# E17-04-ISO_SPI.net
KiCad netlist of a schematic drawn in Altium Designer
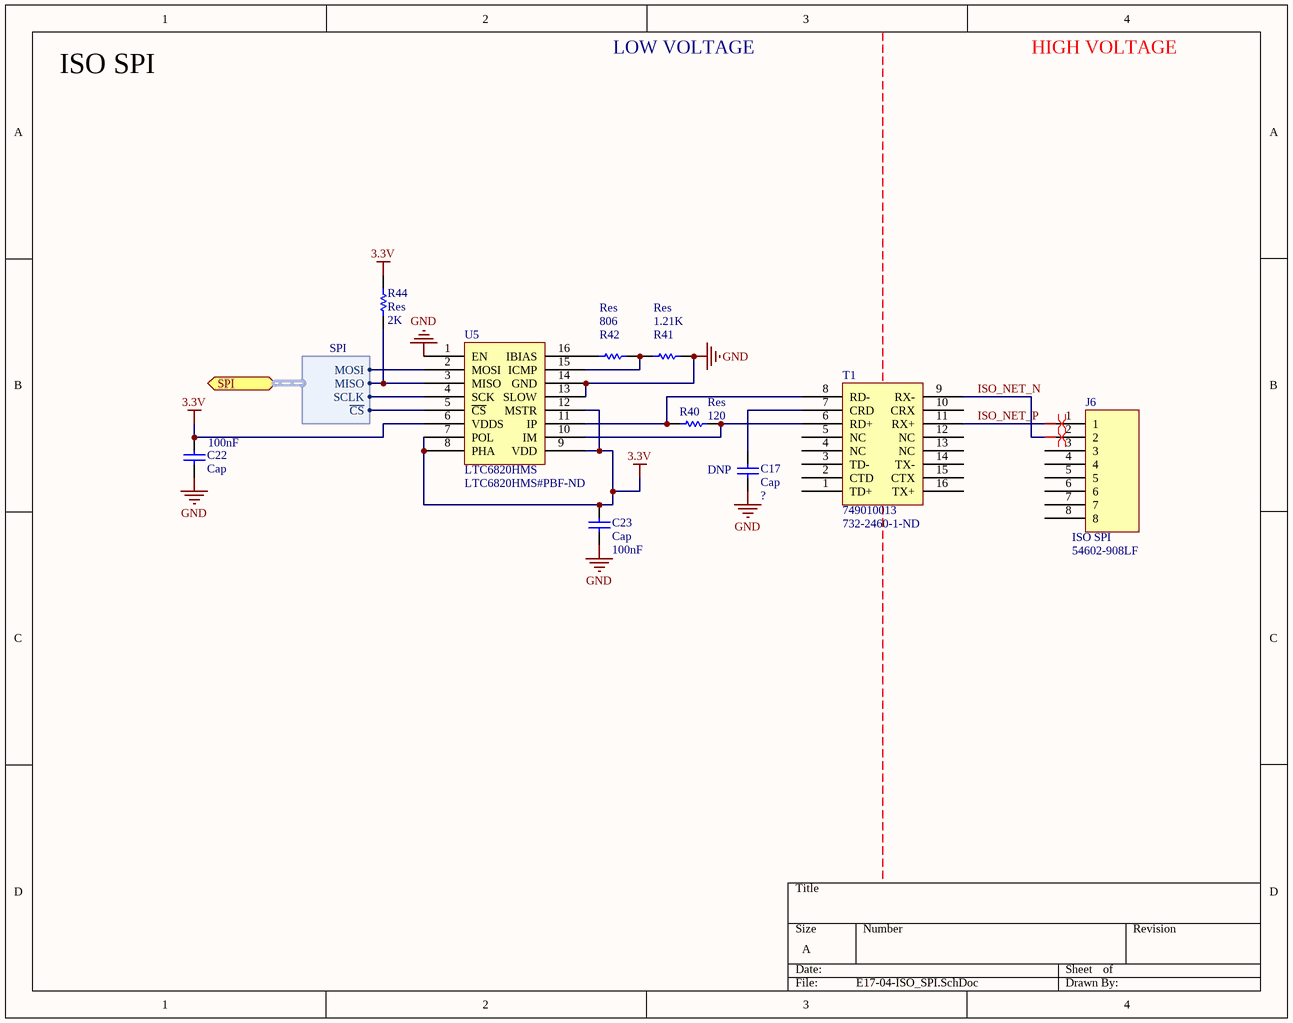
[diagram p0: E17-04-ISO_SPI.SchDoc]

(export (version "E")
  (design (tool "Eeschema 10.0.6"))
  (components
    (comp (ref "C17")
      (value "Cap")
      (footprint "C0805")
      (description "Capacitor")
      (fields
        (field (name "ALTIUM_VALUE") "?")
        (field (name "STUFF") "DNP")
        (field (name "PUBLISHER") "Altium Limited")
      )
      (libsource (lib "Capacitors") (part "Cap"))
    )
    (comp (ref "C22")
      (value "Cap")
      (footprint "C0805")
      (description "Capacitor")
      (fields (field (name "ALTIUM_VALUE") "100nF") (field (name "PUBLISHER") "Altium Limited"))
      (libsource (lib "Capacitors") (part "Cap"))
    )
    (comp (ref "C23")
      (value "Cap")
      (footprint "C0805")
      (description "Capacitor")
      (fields (field (name "ALTIUM_VALUE") "100nF") (field (name "PUBLISHER") "Altium Limited"))
      (libsource (lib "Capacitors") (part "Cap"))
    )
    (comp (ref "J6")
      (value "ISO SPI")
      (footprint "54602-908LF")
      (description "CONN MOD JACK R/A 8P8C")
      (fields (field (name "MPN") "54602-908LF"))
      (libsource (lib "Connectors and Headers") (part "54602-908LF"))
    )
    (comp (ref "R40")
      (value "Res")
      (footprint "2012[0805]")
      (description "Surface Mount Resistor")
      (fields (field (name "ALTIUM_VALUE") "120") (field (name "PUBLISHER") "Altium Limited"))
      (libsource (lib "Resistors") (part "Res"))
    )
    (comp (ref "R41")
      (value "Res")
      (footprint "2012[0805]")
      (description "Surface Mount Resistor")
      (fields (field (name "ALTIUM_VALUE") "1.21K") (field (name "PUBLISHER") "Altium Limited"))
      (libsource (lib "Resistors") (part "Res"))
    )
    (comp (ref "R42")
      (value "Res")
      (footprint "2012[0805]")
      (description "Surface Mount Resistor")
      (fields (field (name "ALTIUM_VALUE") "806") (field (name "PUBLISHER") "Altium Limited"))
      (libsource (lib "Resistors") (part "Res"))
    )
    (comp (ref "R44")
      (value "Res")
      (footprint "2012[0805]")
      (description "Surface Mount Resistor")
      (fields (field (name "ALTIUM_VALUE") "2K") (field (name "PUBLISHER") "Altium Limited"))
      (libsource (lib "Resistors") (part "Res"))
    )
    (comp (ref "T1")
      (value "749010013")
      (footprint "749010013")
      (description "TRANSFORMER LAN 10/100 SMD")
      (fields (field (name "SUPPLIER PART NUMBER 1") "732-2460-1-ND"))
      (libsource (lib "Isolation Circuits") (part "749010013"))
    )
    (comp (ref "U5")
      (value "LTC6820HMS")
      (footprint "LTC6820HMS")
      (description "IC COMM INTERFACE ISOSPI")
      (fields (field (name "SUPPLIER PART NUMBER 1") "LTC6820HMS#PBF-ND"))
      (libsource (lib "Isolation Circuits") (part "LTC6820HMS"))
    )
  )
  (nets
    (net (code "2") (name "/ISO_NET_N") (class "Default")
      (node (ref "J6") (pin "2") (pinfunction "2_2") (pintype "passive"))
      (node (ref "T1") (pin "9") (pinfunction "RX-_9") (pintype "passive"))
    )
    (net (code "3") (name "/ISO_NET_P") (class "Default")
      (node (ref "J6") (pin "1") (pinfunction "1_1") (pintype "passive"))
      (node (ref "T1") (pin "11") (pinfunction "RX+_11") (pintype "passive"))
    )
    (net (code "4") (name "/MISO") (class "Default")
      (node (ref "R44") (pin "2") (pinfunction "2_2") (pintype "passive"))
      (node (ref "U5") (pin "3") (pinfunction "MISO_3") (pintype "passive"))
    )
    (net (code "5") (name "/MOSI") (class "Default")
      (node (ref "U5") (pin "2") (pinfunction "MOSI_2") (pintype "passive"))
    )
    (net (code "6") (name "/SCLK") (class "Default")
      (node (ref "U5") (pin "4") (pinfunction "SCK_4") (pintype "passive"))
    )
    (net (code "8") (name "/~{CS}") (class "Default")
      (node (ref "U5") (pin "5") (pinfunction "~{CS}_5") (pintype "passive"))
    )
    (net (code "9") (name "3.3V") (class "Default")
      (node (ref "C22") (pin "2") (pinfunction "2_2") (pintype "passive"))
      (node (ref "C23") (pin "2") (pinfunction "2_2") (pintype "passive"))
      (node (ref "R44") (pin "1") (pinfunction "1_1") (pintype "passive"))
      (node (ref "U5") (pin "12") (pinfunction "MSTR_12") (pintype "passive"))
      (node (ref "U5") (pin "6") (pinfunction "VDDS_6") (pintype "passive"))
      (node (ref "U5") (pin "7") (pinfunction "POL_7") (pintype "passive"))
      (node (ref "U5") (pin "8") (pinfunction "PHA_8") (pintype "passive"))
      (node (ref "U5") (pin "9") (pinfunction "VDD_9") (pintype "passive"))
    )
    (net (code "10") (name "GND") (class "Default")
      (node (ref "C17") (pin "1") (pinfunction "1_1") (pintype "passive"))
      (node (ref "C22") (pin "1") (pinfunction "1_1") (pintype "passive"))
      (node (ref "C23") (pin "1") (pinfunction "1_1") (pintype "passive"))
      (node (ref "R41") (pin "1") (pinfunction "1_1") (pintype "passive"))
      (node (ref "U5") (pin "1") (pinfunction "EN_1") (pintype "passive"))
      (node (ref "U5") (pin "13") (pinfunction "SLOW_13") (pintype "passive"))
      (node (ref "U5") (pin "14") (pinfunction "GND_14") (pintype "passive"))
    )
    (net (code "11") (name "Net-(T1-CRD)") (class "Default")
      (node (ref "C17") (pin "2") (pinfunction "2_2") (pintype "passive"))
      (node (ref "T1") (pin "7") (pinfunction "CRD_7") (pintype "passive"))
    )
    (net (code "12") (name "Net-(T1-RD+)") (class "Default")
      (node (ref "R40") (pin "1") (pinfunction "1_1") (pintype "passive"))
      (node (ref "T1") (pin "6") (pinfunction "RD+_6") (pintype "passive"))
      (node (ref "U5") (pin "10") (pinfunction "IM_10") (pintype "passive"))
    )
    (net (code "13") (name "Net-(T1-RD-)") (class "Default")
      (node (ref "R40") (pin "2") (pinfunction "2_2") (pintype "passive"))
      (node (ref "T1") (pin "8") (pinfunction "RD-_8") (pintype "passive"))
      (node (ref "U5") (pin "11") (pinfunction "IP_11") (pintype "passive"))
    )
    (net (code "14") (name "Net-(U5-IBIAS)") (class "Default")
      (node (ref "R42") (pin "2") (pinfunction "2_2") (pintype "passive"))
      (node (ref "U5") (pin "16") (pinfunction "IBIAS_16") (pintype "passive"))
    )
    (net (code "15") (name "Net-(U5-ICMP)") (class "Default")
      (node (ref "R41") (pin "2") (pinfunction "2_2") (pintype "passive"))
      (node (ref "R42") (pin "1") (pinfunction "1_1") (pintype "passive"))
      (node (ref "U5") (pin "15") (pinfunction "ICMP_15") (pintype "passive"))
    )
    (net (code "16") (name "unconnected-(J6-Pad3)") (class "Default")
      (node (ref "J6") (pin "3") (pinfunction "3_3") (pintype "passive"))
    )
    (net (code "17") (name "unconnected-(J6-Pad4)") (class "Default")
      (node (ref "J6") (pin "4") (pinfunction "4_4") (pintype "passive"))
    )
    (net (code "18") (name "unconnected-(J6-Pad5)") (class "Default")
      (node (ref "J6") (pin "5") (pinfunction "5_5") (pintype "passive"))
    )
    (net (code "19") (name "unconnected-(J6-Pad6)") (class "Default")
      (node (ref "J6") (pin "6") (pinfunction "6_6") (pintype "passive"))
    )
    (net (code "20") (name "unconnected-(J6-Pad7)") (class "Default")
      (node (ref "J6") (pin "7") (pinfunction "7_7") (pintype "passive"))
    )
    (net (code "21") (name "unconnected-(J6-Pad8)") (class "Default")
      (node (ref "J6") (pin "8") (pinfunction "8_8") (pintype "passive"))
    )
    (net (code "22") (name "unconnected-(T1-CRX-Pad10)") (class "Default")
      (node (ref "T1") (pin "10") (pinfunction "CRX_10") (pintype "passive"))
    )
    (net (code "23") (name "unconnected-(T1-CTD-Pad2)") (class "Default")
      (node (ref "T1") (pin "2") (pinfunction "CTD_2") (pintype "passive"))
    )
    (net (code "24") (name "unconnected-(T1-CTX-Pad15)") (class "Default")
      (node (ref "T1") (pin "15") (pinfunction "CTX_15") (pintype "passive"))
    )
    (net (code "25") (name "unconnected-(T1-NC-Pad4)") (class "Default")
      (node (ref "T1") (pin "4") (pinfunction "NC_4") (pintype "passive"))
    )
    (net (code "26") (name "unconnected-(T1-NC-Pad5)") (class "Default")
      (node (ref "T1") (pin "5") (pinfunction "NC_5") (pintype "passive"))
    )
    (net (code "27") (name "unconnected-(T1-NC-Pad12)") (class "Default")
      (node (ref "T1") (pin "12") (pinfunction "NC_12") (pintype "passive"))
    )
    (net (code "28") (name "unconnected-(T1-NC-Pad13)") (class "Default")
      (node (ref "T1") (pin "13") (pinfunction "NC_13") (pintype "passive"))
    )
    (net (code "29") (name "unconnected-(T1-TD+-Pad1)") (class "Default")
      (node (ref "T1") (pin "1") (pinfunction "TD+_1") (pintype "passive"))
    )
    (net (code "30") (name "unconnected-(T1-TD--Pad3)") (class "Default")
      (node (ref "T1") (pin "3") (pinfunction "TD-_3") (pintype "passive"))
    )
    (net (code "31") (name "unconnected-(T1-TX+-Pad16)") (class "Default")
      (node (ref "T1") (pin "16") (pinfunction "TX+_16") (pintype "passive"))
    )
    (net (code "32") (name "unconnected-(T1-TX--Pad14)") (class "Default")
      (node (ref "T1") (pin "14") (pinfunction "TX-_14") (pintype "passive"))
    )
  )
)
